# Sheet2_1.net
KiCad netlist of a schematic drawn in Altium Designer
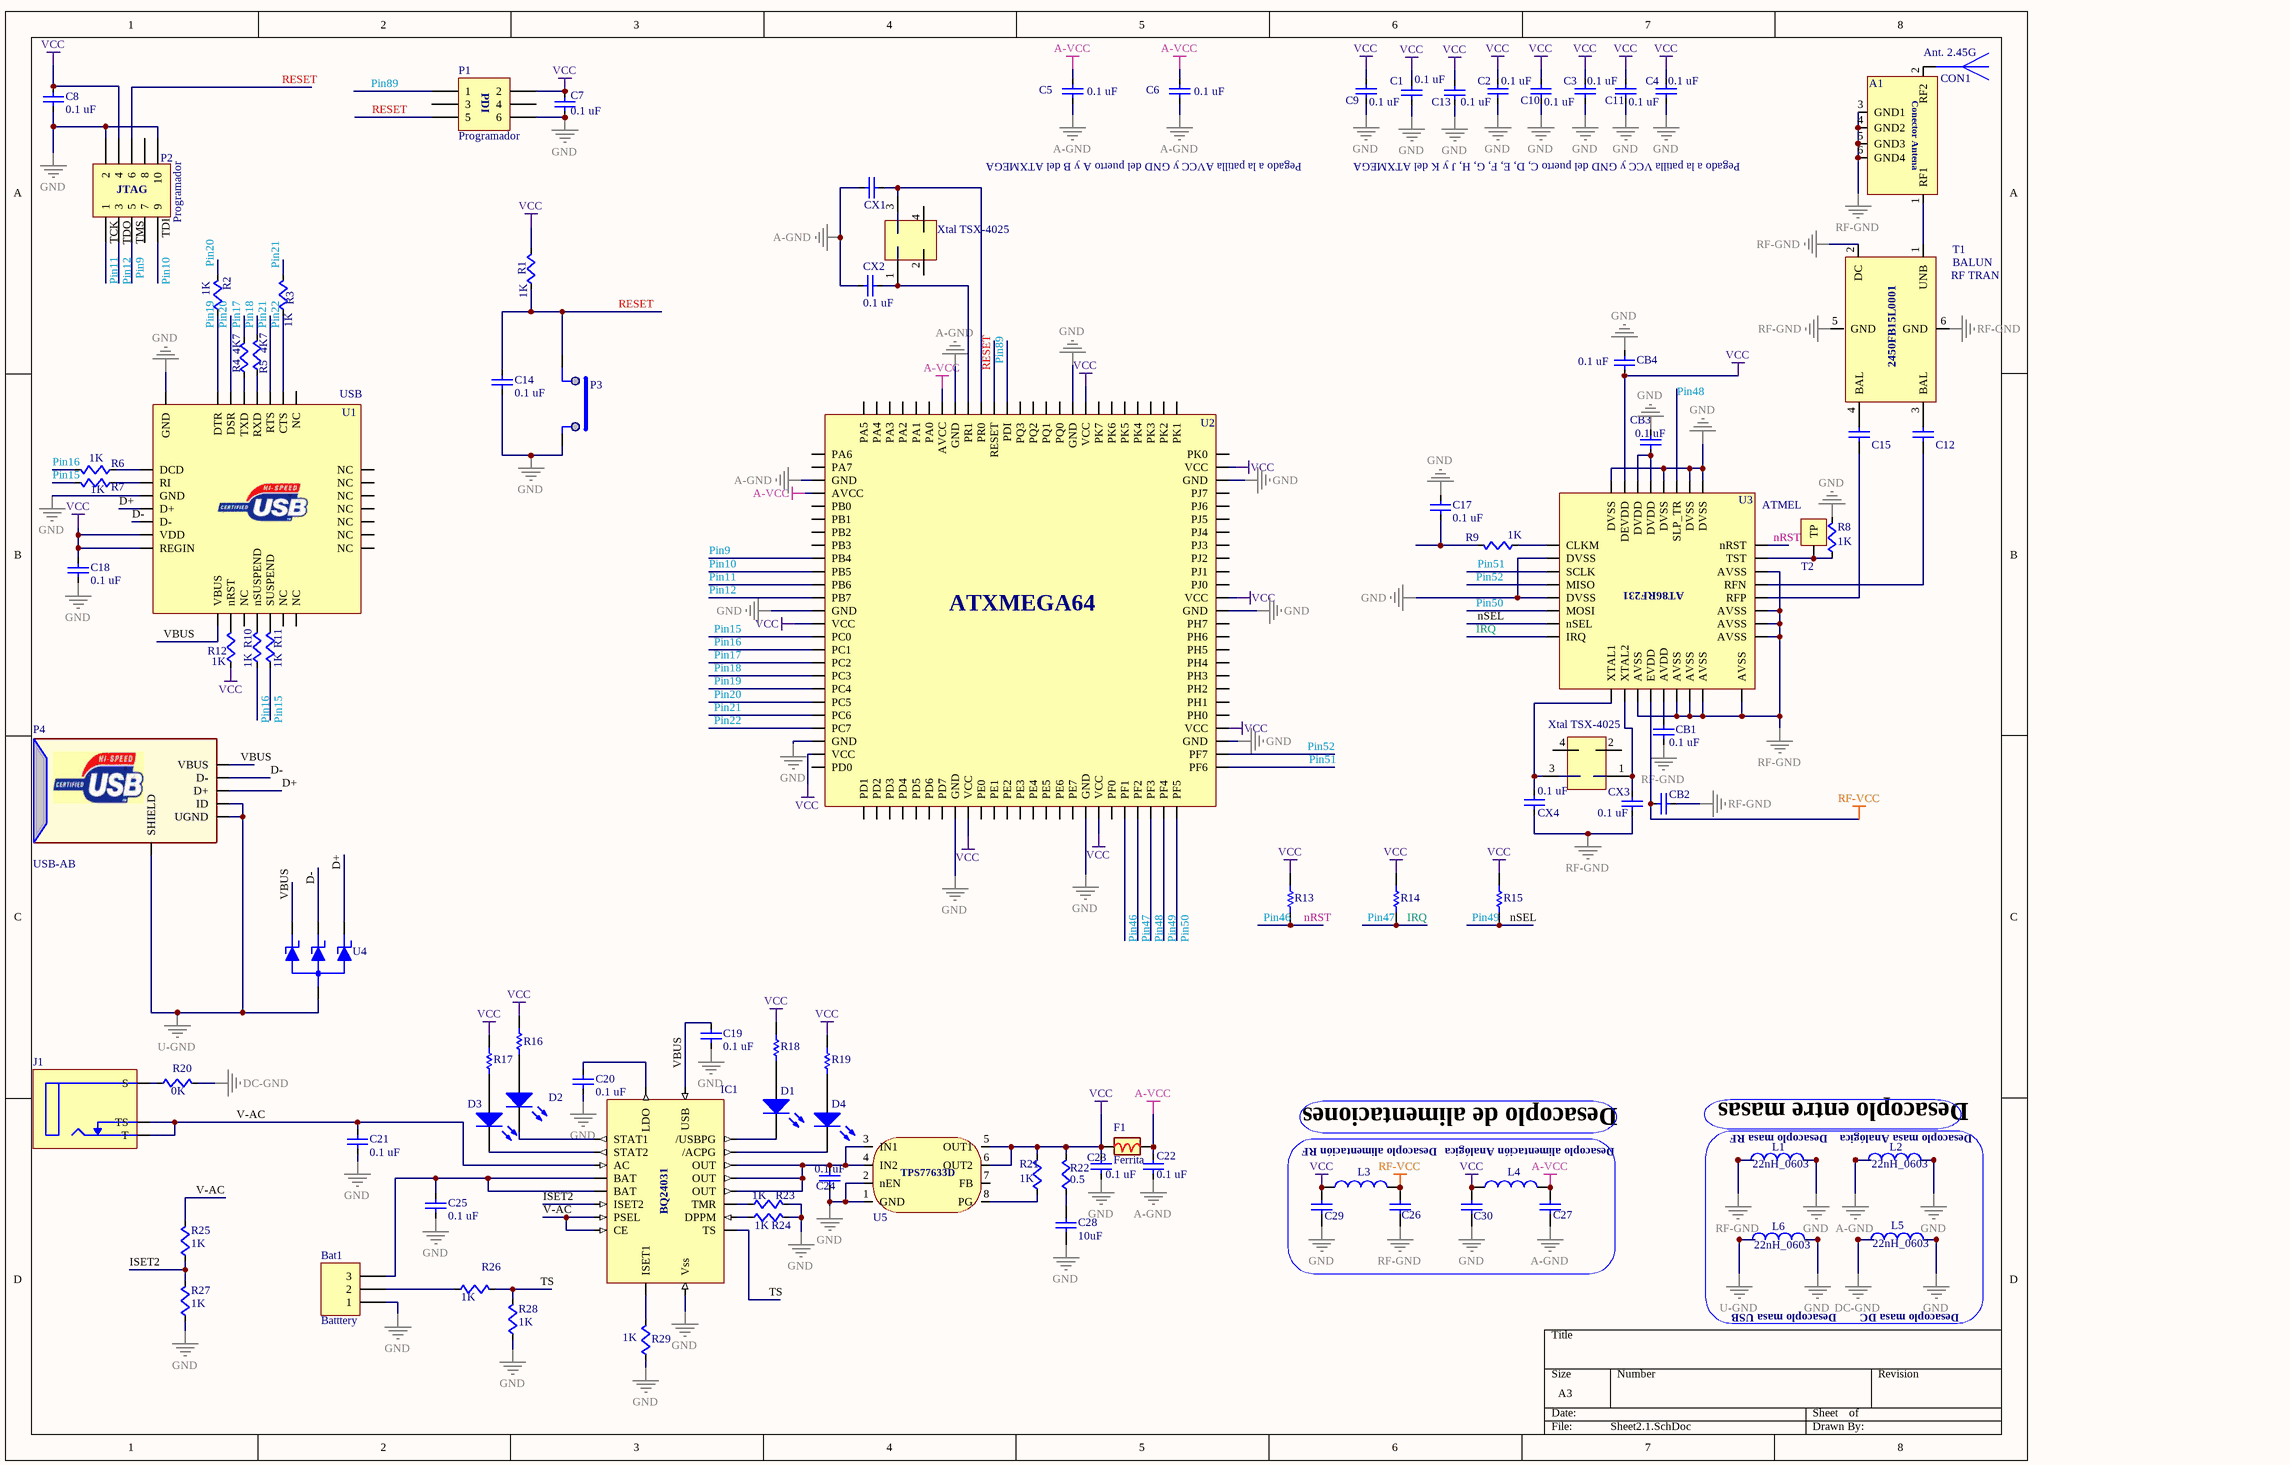
[diagram p0: Sheet2.1.SchDoc]

(export (version "E")
  (design (tool "Eeschema 10.0.6"))
  (components
    (comp (ref "A1")
      (value "Ant. 2.45G")
      (footprint "ANTENNA CHIP")
      (description "ANTENNA CHIP 2.4GHZ")
      (libsource (lib "Mia") (part "2450AT18A100"))
    )
    (comp (ref "Bat1")
      (value "Batttery")
      (footprint "HDR1X3")
      (description "Header, 3-Pin")
      (fields (field (name "PUBLISHER") "Altium Limited"))
      (libsource (lib "Mia") (part "Header 3"))
    )
    (comp (ref "C1")
      (value "C")
      (footprint "0402")
      (description "CONDENSADOR")
      (fields (field (name "VALOR") "0.1 uF"))
      (libsource (lib "Mia") (part "C"))
    )
    (comp (ref "C2")
      (value "C")
      (footprint "0402")
      (description "CONDENSADOR")
      (fields (field (name "VALOR") "0.1 uF"))
      (libsource (lib "Mia") (part "C"))
    )
    (comp (ref "C3")
      (value "C")
      (footprint "0402")
      (description "CONDENSADOR")
      (fields (field (name "VALOR") "0.1 uF"))
      (libsource (lib "Mia") (part "C"))
    )
    (comp (ref "C4")
      (value "C")
      (footprint "0402")
      (description "CONDENSADOR")
      (fields (field (name "VALOR") "0.1 uF"))
      (libsource (lib "Mia") (part "C"))
    )
    (comp (ref "C5")
      (value "C")
      (footprint "0402")
      (description "CONDENSADOR")
      (fields (field (name "VALOR") "0.1 uF"))
      (libsource (lib "Mia") (part "C"))
    )
    (comp (ref "C6")
      (value "C")
      (footprint "0402")
      (description "CONDENSADOR")
      (fields (field (name "VALOR") "0.1 uF"))
      (libsource (lib "Mia") (part "C"))
    )
    (comp (ref "C7")
      (value "C")
      (footprint "0402")
      (description "CONDENSADOR")
      (fields (field (name "VALOR") "0.1 uF"))
      (libsource (lib "Mia") (part "C"))
    )
    (comp (ref "C8")
      (value "C")
      (footprint "0402")
      (description "CONDENSADOR")
      (fields (field (name "VALOR") "0.1 uF"))
      (libsource (lib "Mia") (part "C"))
    )
    (comp (ref "C9")
      (value "C")
      (footprint "0402")
      (description "CONDENSADOR")
      (fields (field (name "VALOR") "0.1 uF"))
      (libsource (lib "Mia") (part "C"))
    )
    (comp (ref "C10")
      (value "C")
      (footprint "0402")
      (description "CONDENSADOR")
      (fields (field (name "VALOR") "0.1 uF"))
      (libsource (lib "Mia") (part "C"))
    )
    (comp (ref "C11")
      (value "C")
      (footprint "0402")
      (description "CONDENSADOR")
      (fields (field (name "VALOR") "0.1 uF"))
      (libsource (lib "Mia") (part "C"))
    )
    (comp (ref "C12")
      (value "22pF_0402")
      (footprint "0402")
      (description "CAP CER 56PF 50V 5% C0G 0402")
      (libsource (lib "Mia") (part "56pF_0402"))
    )
    (comp (ref "C13")
      (value "C")
      (footprint "0402")
      (description "CONDENSADOR")
      (fields (field (name "VALOR") "0.1 uF"))
      (libsource (lib "Mia") (part "C"))
    )
    (comp (ref "C14")
      (value "C")
      (footprint "0402")
      (description "CONDENSADOR")
      (fields (field (name "VALOR") "0.1 uF"))
      (libsource (lib "Mia") (part "C"))
    )
    (comp (ref "C15")
      (value "22pF_0402")
      (footprint "0402")
      (description "CAP CER 56PF 50V 5% C0G 0402")
      (libsource (lib "Mia") (part "56pF_0402"))
    )
    (comp (ref "C17")
      (value "C")
      (footprint "0402")
      (description "CONDENSADOR")
      (fields (field (name "VALOR") "0.1 uF"))
      (libsource (lib "Mia") (part "C"))
    )
    (comp (ref "C18")
      (value "C")
      (footprint "0402")
      (description "CONDENSADOR")
      (fields (field (name "VALOR") "0.1 uF"))
      (libsource (lib "Mia") (part "C"))
    )
    (comp (ref "C19")
      (value "C")
      (footprint "0402")
      (description "CONDENSADOR")
      (fields (field (name "VALOR") "0.1 uF"))
      (libsource (lib "Mia") (part "C"))
    )
    (comp (ref "C20")
      (value "C")
      (footprint "0402")
      (description "CONDENSADOR")
      (fields (field (name "VALOR") "0.1 uF"))
      (libsource (lib "Mia") (part "C"))
    )
    (comp (ref "C21")
      (value "C")
      (footprint "0402")
      (description "CONDENSADOR")
      (fields (field (name "VALOR") "0.1 uF"))
      (libsource (lib "Mia") (part "C"))
    )
    (comp (ref "C22")
      (value "C")
      (footprint "0402")
      (description "CONDENSADOR")
      (fields (field (name "VALOR") "0.1 uF"))
      (libsource (lib "Mia") (part "C"))
    )
    (comp (ref "C23")
      (value "C")
      (footprint "0402")
      (description "CONDENSADOR")
      (fields (field (name "VALOR") "0.1 uF"))
      (libsource (lib "Mia") (part "C"))
    )
    (comp (ref "C24")
      (value "C")
      (footprint "0402")
      (description "CONDENSADOR")
      (fields (field (name "VALOR") "0.1 uF"))
      (libsource (lib "Mia") (part "C"))
    )
    (comp (ref "C25")
      (value "C")
      (footprint "0402")
      (description "CONDENSADOR")
      (fields (field (name "VALOR") "0.1 uF"))
      (libsource (lib "Mia") (part "C"))
    )
    (comp (ref "C26")
      (value "100nF_0805")
      (footprint "0805")
      (description "CAP CER 100PF 630V X7R 0805")
      (libsource (lib "Mia") (part "100nF_0805"))
    )
    (comp (ref "C27")
      (value "100nF_0805")
      (footprint "0805")
      (description "CAP CER 100PF 630V X7R 0805")
      (libsource (lib "Mia") (part "100nF_0805"))
    )
    (comp (ref "C28")
      (value "10uF")
      (footprint "0805")
      (description "CAP CER 10UF 10V Y5V 0805")
      (libsource (lib "Mia") (part "10uF_0805"))
    )
    (comp (ref "C29")
      (value "100nF_0805")
      (footprint "0805")
      (description "CAP CER 100PF 630V X7R 0805")
      (libsource (lib "Mia") (part "100nF_0805"))
    )
    (comp (ref "C30")
      (value "100nF_0805")
      (footprint "0805")
      (description "CAP CER 100PF 630V X7R 0805")
      (libsource (lib "Mia") (part "100nF_0805"))
    )
    (comp (ref "CB1")
      (value "C")
      (footprint "0402")
      (description "CONDENSADOR")
      (fields (field (name "VALOR") "0.1 uF"))
      (libsource (lib "Mia") (part "C"))
    )
    (comp (ref "CB2")
      (value "C")
      (footprint "0402")
      (description "CONDENSADOR")
      (fields (field (name "VALOR") "0.1 uF"))
      (libsource (lib "Mia") (part "C"))
    )
    (comp (ref "CB3")
      (value "C")
      (footprint "0402")
      (description "CONDENSADOR")
      (fields (field (name "VALOR") "0.1 uF"))
      (libsource (lib "Mia") (part "C"))
    )
    (comp (ref "CB4")
      (value "C")
      (footprint "0402")
      (description "CONDENSADOR")
      (fields (field (name "VALOR") "0.1 uF"))
      (libsource (lib "Mia") (part "C"))
    )
    (comp (ref "CON1")
      (value "Conector Antena")
      (footprint "MM8430-2600_Coaxial Connectors")
      (description "CONN MW COAXIAL WITH SWITCH")
      (libsource (lib "Mia") (part "CON ANT-MM8430-2600RA1"))
    )
    (comp (ref "CX1")
      (value "C")
      (footprint "0402")
      (description "CONDENSADOR")
      (libsource (lib "Mia") (part "C"))
    )
    (comp (ref "CX2")
      (value "C")
      (footprint "0402")
      (description "CONDENSADOR")
      (fields (field (name "VALOR") "0.1 uF"))
      (libsource (lib "Mia") (part "C"))
    )
    (comp (ref "CX3")
      (value "C")
      (footprint "0402")
      (description "CONDENSADOR")
      (fields (field (name "VALOR") "0.1 uF"))
      (libsource (lib "Mia") (part "C"))
    )
    (comp (ref "CX4")
      (value "C")
      (footprint "0402")
      (description "CONDENSADOR")
      (libsource (lib "Mia") (part "C"))
    )
    (comp (ref "D1")
      (value "Diodo Led")
      (footprint "Diode Led")
      (description "Typical INFRARED GaAs LED")
      (libsource (lib "Mia") (part "LTST-C230CKT"))
    )
    (comp (ref "D2")
      (value "Diodo Led")
      (footprint "Diode Led")
      (description "Typical INFRARED GaAs LED")
      (libsource (lib "Mia") (part "LTST-C230CKT"))
    )
    (comp (ref "D3")
      (value "Diodo Led")
      (footprint "Diode Led")
      (description "Typical INFRARED GaAs LED")
      (libsource (lib "Mia") (part "LTST-C230CKT"))
    )
    (comp (ref "D4")
      (value "Diodo Led")
      (footprint "Diode Led")
      (description "Typical INFRARED GaAs LED")
      (libsource (lib "Mia") (part "LTST-C230CKT"))
    )
    (comp (ref "F1")
      (value "Ferrita")
      (footprint "0603")
      (description "Chip Ferrite Beads")
      (libsource (lib "Mia") (part "BLM21AH102SN1"))
    )
    (comp (ref "IC1")
      (value "BQ24031")
      (footprint "BQ24031")
      (description "IC PWR MANAGEMENT SYSTEM 20-QFN")
      (libsource (lib "Mia") (part "BQ24031"))
    )
    (comp (ref "J1")
      (value "CAMSHOT")
      (footprint "MJ-2509N")
      (description "CONN MONO JACK 2.5MM PCB MNT")
      (libsource (lib "*") (part "MJ-2509N_1"))
    )
    (comp (ref "L1")
      (value "22nH_0603")
      (footprint "0603")
      (description "CER INDUCTOR 22NH 0603")
      (libsource (lib "Mia") (part "22nH_0603"))
    )
    (comp (ref "L2")
      (value "22nH_0603")
      (footprint "0603")
      (description "CER INDUCTOR 22NH 0603")
      (libsource (lib "Mia") (part "22nH_0603"))
    )
    (comp (ref "L3")
      (value "22nH_0603")
      (footprint "0603")
      (description "CER INDUCTOR 22NH 0603")
      (libsource (lib "Mia") (part "22nH_0603"))
    )
    (comp (ref "L4")
      (value "22nH_0603")
      (footprint "0603")
      (description "CER INDUCTOR 22NH 0603")
      (libsource (lib "Mia") (part "22nH_0603"))
    )
    (comp (ref "L5")
      (value "22nH_0603")
      (footprint "0603")
      (description "CER INDUCTOR 22NH 0603")
      (libsource (lib "Mia") (part "22nH_0603"))
    )
    (comp (ref "L6")
      (value "22nH_0603")
      (footprint "0603")
      (description "CER INDUCTOR 22NH 0603")
      (libsource (lib "Mia") (part "22nH_0603"))
    )
    (comp (ref "P1")
      (value "Programador")
      (footprint "HDR2X3")
      (description "Header, 3-Pin, Dual row")
      (fields (field (name "PUBLISHER") "Altium Limited"))
      (libsource (lib "Mia") (part "Header 3X2"))
    )
    (comp (ref "P2")
      (value "Programador")
      (footprint "HDR2X5")
      (description "Header, 5-Pin, Dual row")
      (fields (field (name "PUBLISHER") "Altium Limited"))
      (libsource (lib "Mia") (part "Header 5X2"))
    )
    (comp (ref "P3")
      (value "Pulsador")
      (footprint "PUSH-BUTTON-W")
      (description "SWITCH TACT 6X3.5MM H=4.3MM 180G")
      (libsource (lib "Mia") (part "PUSHBUTTON"))
    )
    (comp (ref "P4")
      (value "USB-AB")
      (footprint "USB-MINI-AB-SMT")
      (description "CONN RECEPT USB 5POS RT ANG SMD")
      (libsource (lib "Mia") (part "WM1722"))
    )
    (comp (ref "R1")
      (value "1K")
      (footprint "0603")
      (description "RESISTENCIA 0402 SMD")
      (fields (field (name "Comment") "R 0402"))
      (libsource (lib "Mia") (part "R 0402"))
    )
    (comp (ref "R2")
      (value "1K")
      (footprint "0603")
      (description "RESISTENCIA 0402 SMD")
      (fields (field (name "Comment") "R 0402"))
      (libsource (lib "Mia") (part "R 0402"))
    )
    (comp (ref "R3")
      (value "1K")
      (footprint "0603")
      (description "RESISTENCIA 0402 SMD")
      (fields (field (name "Comment") "R 0402"))
      (libsource (lib "Mia") (part "R 0402"))
    )
    (comp (ref "R4")
      (value "4K7")
      (footprint "0603")
      (description "RESISTENCIA 0402 SMD")
      (fields (field (name "Comment") "R 0402"))
      (libsource (lib "Mia") (part "R 0402"))
    )
    (comp (ref "R5")
      (value "4K7")
      (footprint "0603")
      (description "RESISTENCIA 0402 SMD")
      (fields (field (name "Comment") "R 0402"))
      (libsource (lib "Mia") (part "R 0402"))
    )
    (comp (ref "R6")
      (value "1K")
      (footprint "0603")
      (description "RESISTENCIA 0402 SMD")
      (fields (field (name "Comment") "R 0402"))
      (libsource (lib "Mia") (part "R 0402"))
    )
    (comp (ref "R7")
      (value "1K")
      (footprint "0603")
      (description "RESISTENCIA 0402 SMD")
      (fields (field (name "Comment") "R 0402"))
      (libsource (lib "Mia") (part "R 0402"))
    )
    (comp (ref "R8")
      (value "1K")
      (footprint "0603")
      (description "RESISTENCIA 0402 SMD")
      (fields (field (name "Comment") "R 0402"))
      (libsource (lib "Mia") (part "R 0402"))
    )
    (comp (ref "R9")
      (value "1K")
      (footprint "0603")
      (description "RESISTENCIA 0402 SMD")
      (fields (field (name "Comment") "R 0402"))
      (libsource (lib "Mia") (part "R 0402"))
    )
    (comp (ref "R10")
      (value "1K")
      (footprint "0603")
      (description "RESISTENCIA 0402 SMD")
      (fields (field (name "Comment") "R 0402"))
      (libsource (lib "Mia") (part "R 0402"))
    )
    (comp (ref "R11")
      (value "1K")
      (footprint "0603")
      (description "RESISTENCIA 0402 SMD")
      (fields (field (name "Comment") "R 0402"))
      (libsource (lib "Mia") (part "R 0402"))
    )
    (comp (ref "R12")
      (value "1K")
      (footprint "0603")
      (description "RESISTENCIA 0402 SMD")
      (fields (field (name "Comment") "R 0402"))
      (libsource (lib "Mia") (part "R 0402"))
    )
    (comp (ref "R13")
      (value "16.9kohm-0805")
      (footprint "0805")
      (description "RES 16.9K OHM 1/8W 1% 0805 SMD")
      (libsource (lib "Mia") (part "16.9kohm-0805"))
    )
    (comp (ref "R14")
      (value "16.9kohm-0805")
      (footprint "0805")
      (description "RES 16.9K OHM 1/8W 1% 0805 SMD")
      (libsource (lib "Mia") (part "16.9kohm-0805"))
    )
    (comp (ref "R15")
      (value "16.9kohm-0805")
      (footprint "0805")
      (description "RES 16.9K OHM 1/8W 1% 0805 SMD")
      (libsource (lib "Mia") (part "16.9kohm-0805"))
    )
    (comp (ref "R16")
      (value "16.9kohm-0805")
      (footprint "0805")
      (description "RES 16.9K OHM 1/8W 1% 0805 SMD")
      (libsource (lib "Mia") (part "16.9kohm-0805"))
    )
    (comp (ref "R17")
      (value "16.9kohm-0805")
      (footprint "0805")
      (description "RES 16.9K OHM 1/8W 1% 0805 SMD")
      (libsource (lib "Mia") (part "16.9kohm-0805"))
    )
    (comp (ref "R18")
      (value "16.9kohm-0805")
      (footprint "0805")
      (description "RES 16.9K OHM 1/8W 1% 0805 SMD")
      (libsource (lib "Mia") (part "16.9kohm-0805"))
    )
    (comp (ref "R19")
      (value "16.9kohm-0805")
      (footprint "0805")
      (description "RES 16.9K OHM 1/8W 1% 0805 SMD")
      (libsource (lib "Mia") (part "16.9kohm-0805"))
    )
    (comp (ref "R20")
      (value "0K")
      (footprint "0603")
      (description "RESISTENCIA 0402 SMD")
      (fields (field (name "Comment") "R 0402"))
      (libsource (lib "Mia") (part "R 0402"))
    )
    (comp (ref "R21")
      (value "1K")
      (footprint "0603")
      (description "RESISTENCIA 0402 SMD")
      (fields (field (name "Comment") "R 0402"))
      (libsource (lib "Mia") (part "R 0402"))
    )
    (comp (ref "R22")
      (value "0.5")
      (footprint "0603")
      (description "RESISTENCIA 0402 SMD")
      (fields (field (name "Comment") "R 0402"))
      (libsource (lib "Mia") (part "R 0402"))
    )
    (comp (ref "R23")
      (value "1K")
      (footprint "0603")
      (description "RESISTENCIA 0402 SMD")
      (fields (field (name "Comment") "R 0402"))
      (libsource (lib "Mia") (part "R 0402"))
    )
    (comp (ref "R24")
      (value "1K")
      (footprint "0603")
      (description "RESISTENCIA 0402 SMD")
      (fields (field (name "Comment") "R 0402"))
      (libsource (lib "Mia") (part "R 0402"))
    )
    (comp (ref "R25")
      (value "1K")
      (footprint "0603")
      (description "RESISTENCIA 0402 SMD")
      (fields (field (name "Comment") "R 0402"))
      (libsource (lib "Mia") (part "R 0402"))
    )
    (comp (ref "R26")
      (value "1K")
      (footprint "0603")
      (description "RESISTENCIA 0402 SMD")
      (fields (field (name "Comment") "R 0402"))
      (libsource (lib "Mia") (part "R 0402"))
    )
    (comp (ref "R27")
      (value "1K")
      (footprint "0603")
      (description "RESISTENCIA 0402 SMD")
      (fields (field (name "Comment") "R 0402"))
      (libsource (lib "Mia") (part "R 0402"))
    )
    (comp (ref "R28")
      (value "1K")
      (footprint "0603")
      (description "RESISTENCIA 0402 SMD")
      (fields (field (name "Comment") "R 0402"))
      (libsource (lib "Mia") (part "R 0402"))
    )
    (comp (ref "R29")
      (value "1K")
      (footprint "0603")
      (description "RESISTENCIA 0402 SMD")
      (fields (field (name "Comment") "R 0402"))
      (libsource (lib "Mia") (part "R 0402"))
    )
    (comp (ref "T1")
      (value "BALUN")
      (footprint "BALUN")
      (description "FILTER BALUN CER CHIP 2.4GHZ")
      (libsource (lib "Mia") (part "2450FB39B100E"))
    )
    (comp (ref "T2")
      (value "TESTPOINT")
      (footprint "TESTPOINT")
      (description "Punto de Test")
      (libsource (lib "Mia") (part "TESTPOINT"))
    )
    (comp (ref "U1")
      (value "USB")
      (footprint "QFN28_5X5")
      (description "IC USB-TO-UART BRIDGE 28MLP")
      (libsource (lib "Mia") (part "CP2102"))
    )
    (comp (ref "U2")
      (value "XMEGA")
      (footprint "Quad100")
      (description "MCU AVR 64K FLASH 1.6V 100-TQFP")
      (libsource (lib "Mia") (part "ATXMEGA64A1"))
    )
    (comp (ref "U3")
      (value "RF TRAN")
      (footprint "QFN32_50")
      (description "IC TXRX ZIGBEE/802.15.4 32QFN")
      (fields (field (name "FABRICANTE") "ATMEL"))
      (libsource (lib "Mia") (part "AT86RF231"))
    )
    (comp (ref "U4")
      (value "TVS")
      (footprint "SOT-143")
      (description "TVS AVAL DIODE ARRAY 3 CH SOT143")
      (libsource (lib "Mia") (part "SP0503BAHTG"))
    )
    (comp (ref "U5")
      (value "TPS77633D")
      (footprint "TPS77633D")
      (description "IC 3.3V 500MA LDO REG 8-SOIC")
      (libsource (lib "Mia") (part "TPS77633D"))
    )
    (comp (ref "Xtal1")
      (value "Xtal TSX-4025")
      (footprint "TSX-4025")
      (description "Cristal 16Mhz")
      (libsource (lib "") (part "Xtal TSX-4025_1"))
    )
    (comp (ref "Xtal2")
      (value "Xtal TSX-4025")
      (footprint "TSX-4025")
      (description "Cristal 16Mhz")
      (libsource (lib "Mia") (part "Xtal TSX-4025"))
    )
  )
  (nets
    (net (code "1") (name "/D+") (class "Default")
      (node (ref "P4") (pin "D+") (pinfunction "D+_D+") (pintype "passive"))
      (node (ref "U1") (pin "4") (pinfunction "D+_4") (pintype "passive"))
      (node (ref "U4") (pin "2") (pinfunction "C_2") (pintype "passive"))
    )
    (net (code "2") (name "/D-") (class "Default")
      (node (ref "P4") (pin "D-") (pinfunction "D-_D-") (pintype "passive"))
      (node (ref "U1") (pin "5") (pinfunction "D-_5") (pintype "passive"))
      (node (ref "U4") (pin "3") (pinfunction "C_3") (pintype "passive"))
    )
    (net (code "3") (name "/IRQ") (class "Default")
      (node (ref "R14") (pin "1") (pinfunction "1_1") (pintype "passive"))
      (node (ref "U2") (pin "47") (pinfunction "PF2_47") (pintype "passive"))
      (node (ref "U3") (pin "24") (pinfunction "IRQ_24") (pintype "passive"))
    )
    (net (code "4") (name "/ISET2") (class "Default")
      (node (ref "IC1") (pin "7") (pinfunction "ISET2_7") (pintype "input"))
      (node (ref "R25") (pin "1") (pinfunction "1_1") (pintype "passive"))
      (node (ref "R27") (pin "2") (pinfunction "2_2") (pintype "passive"))
    )
    (net (code "5") (name "/Pin9") (class "Default")
      (node (ref "P2") (pin "5") (pinfunction "5_5") (pintype "passive"))
      (node (ref "U2") (pin "9") (pinfunction "PB4_9") (pintype "passive"))
    )
    (net (code "6") (name "/Pin10") (class "Default")
      (node (ref "P2") (pin "9") (pinfunction "9_9") (pintype "passive"))
      (node (ref "U2") (pin "10") (pinfunction "PB5_10") (pintype "passive"))
    )
    (net (code "7") (name "/Pin11") (class "Default")
      (node (ref "P2") (pin "1") (pinfunction "1_1") (pintype "passive"))
      (node (ref "U2") (pin "11") (pinfunction "PB6_11") (pintype "passive"))
    )
    (net (code "8") (name "/Pin12") (class "Default")
      (node (ref "P2") (pin "3") (pinfunction "3_3") (pintype "passive"))
      (node (ref "U2") (pin "12") (pinfunction "PB7_12") (pintype "passive"))
    )
    (net (code "9") (name "/Pin15") (class "Default")
      (node (ref "R11") (pin "1") (pinfunction "1_1") (pintype "passive"))
      (node (ref "R7") (pin "2") (pinfunction "2_2") (pintype "passive"))
      (node (ref "U2") (pin "15") (pinfunction "PC0_15") (pintype "passive"))
    )
    (net (code "10") (name "/Pin16") (class "Default")
      (node (ref "R10") (pin "1") (pinfunction "1_1") (pintype "passive"))
      (node (ref "R6") (pin "2") (pinfunction "2_2") (pintype "passive"))
      (node (ref "U2") (pin "16") (pinfunction "PC1_16") (pintype "passive"))
    )
    (net (code "11") (name "/Pin17") (class "Default")
      (node (ref "R4") (pin "2") (pinfunction "2_2") (pintype "passive"))
      (node (ref "U2") (pin "17") (pinfunction "PC2_17") (pintype "passive"))
    )
    (net (code "12") (name "/Pin18") (class "Default")
      (node (ref "R5") (pin "2") (pinfunction "2_2") (pintype "passive"))
      (node (ref "U2") (pin "18") (pinfunction "PC3_18") (pintype "passive"))
    )
    (net (code "13") (name "/Pin19") (class "Default")
      (node (ref "R2") (pin "1") (pinfunction "1_1") (pintype "passive"))
      (node (ref "U1") (pin "28") (pinfunction "DTR_28") (pintype "passive"))
      (node (ref "U2") (pin "19") (pinfunction "PC4_19") (pintype "passive"))
    )
    (net (code "14") (name "/Pin20") (class "Default")
      (node (ref "R2") (pin "2") (pinfunction "2_2") (pintype "passive"))
      (node (ref "U1") (pin "27") (pinfunction "DSR_27") (pintype "passive"))
      (node (ref "U2") (pin "20") (pinfunction "PC5_20") (pintype "passive"))
    )
    (net (code "15") (name "/Pin21") (class "Default")
      (node (ref "R3") (pin "2") (pinfunction "2_2") (pintype "passive"))
      (node (ref "U1") (pin "24") (pinfunction "RTS_24") (pintype "passive"))
      (node (ref "U2") (pin "21") (pinfunction "PC6_21") (pintype "passive"))
    )
    (net (code "16") (name "/Pin22") (class "Default")
      (node (ref "R3") (pin "1") (pinfunction "1_1") (pintype "passive"))
      (node (ref "U1") (pin "23") (pinfunction "CTS_23") (pintype "passive"))
      (node (ref "U2") (pin "22") (pinfunction "PC7_22") (pintype "passive"))
    )
    (net (code "17") (name "/Pin46") (class "Default")
      (node (ref "R13") (pin "1") (pinfunction "1_1") (pintype "passive"))
      (node (ref "U2") (pin "46") (pinfunction "PF1_46") (pintype "passive"))
      (node (ref "U3") (pin "8") (pinfunction "nRST_8") (pintype "passive"))
    )
    (net (code "18") (name "/Pin48") (class "Default")
      (node (ref "U2") (pin "48") (pinfunction "PF3_48") (pintype "passive"))
      (node (ref "U3") (pin "11") (pinfunction "SLP_TR_11") (pintype "passive"))
    )
    (net (code "19") (name "/Pin49") (class "Default")
      (node (ref "R15") (pin "1") (pinfunction "1_1") (pintype "passive"))
      (node (ref "U2") (pin "49") (pinfunction "PF4_49") (pintype "passive"))
      (node (ref "U3") (pin "23") (pinfunction "nSEL_23") (pintype "passive"))
    )
    (net (code "20") (name "/Pin50") (class "Default")
      (node (ref "U2") (pin "50") (pinfunction "PF5_50") (pintype "passive"))
      (node (ref "U3") (pin "22") (pinfunction "MOSI_22") (pintype "passive"))
    )
    (net (code "21") (name "/Pin51") (class "Default")
      (node (ref "U2") (pin "51") (pinfunction "PF6_51") (pintype "passive"))
      (node (ref "U3") (pin "19") (pinfunction "SCLK_19") (pintype "passive"))
    )
    (net (code "22") (name "/Pin52") (class "Default")
      (node (ref "U2") (pin "52") (pinfunction "PF7_52") (pintype "passive"))
      (node (ref "U3") (pin "20") (pinfunction "MISO_20") (pintype "passive"))
    )
    (net (code "23") (name "/Pin89") (class "Default")
      (node (ref "P1") (pin "1") (pinfunction "1_1") (pintype "passive"))
      (node (ref "U2") (pin "89") (pinfunction "PDI_89") (pintype "passive"))
    )
    (net (code "24") (name "/RESET") (class "Default")
      (node (ref "C14") (pin "1") (pinfunction "1_1") (pintype "passive"))
      (node (ref "P1") (pin "5") (pinfunction "5_5") (pintype "passive"))
      (node (ref "P2") (pin "6") (pinfunction "6_6") (pintype "passive"))
      (node (ref "P3") (pin "1") (pinfunction "1_1") (pintype "passive"))
      (node (ref "R1") (pin "1") (pinfunction "1_1") (pintype "passive"))
      (node (ref "U2") (pin "90") (pinfunction "RESET_90") (pintype "passive"))
    )
    (net (code "29") (name "/TS") (class "Default")
      (node (ref "IC1") (pin "12") (pinfunction "TS_12") (pintype "bidirectional"))
      (node (ref "R26") (pin "2") (pinfunction "2_2") (pintype "passive"))
      (node (ref "R28") (pin "2") (pinfunction "2_2") (pintype "passive"))
    )
    (net (code "30") (name "/V-AC") (class "Default")
      (node (ref "C21") (pin "1") (pinfunction "1_1") (pintype "passive"))
      (node (ref "IC1") (pin "4") (pinfunction "AC_4") (pintype "input"))
      (node (ref "IC1") (pin "8") (pinfunction "PSEL_8") (pintype "input"))
      (node (ref "IC1") (pin "9") (pinfunction "CE_9") (pintype "input"))
      (node (ref "J1") (pin "2") (pinfunction "T_2") (pintype "passive"))
      (node (ref "J1") (pin "3") (pinfunction "TS_3") (pintype "passive"))
      (node (ref "R25") (pin "2") (pinfunction "2_2") (pintype "passive"))
    )
    (net (code "31") (name "/VBUS") (class "Default")
      (node (ref "C19") (pin "1") (pinfunction "1_1") (pintype "passive"))
      (node (ref "IC1") (pin "20") (pinfunction "USB_20") (pintype "input"))
      (node (ref "P4") (pin "VBUS") (pinfunction "VBUS_VBUS") (pintype "passive"))
      (node (ref "U1") (pin "8") (pinfunction "VBUS_8") (pintype "passive"))
      (node (ref "U4") (pin "4") (pinfunction "C_4") (pintype "passive"))
    )
    (net (code "32") (name "A-GND") (class "Default")
      (node (ref "C22") (pin "2") (pinfunction "2_2") (pintype "passive"))
      (node (ref "C27") (pin "1") (pinfunction "1_1") (pintype "passive"))
      (node (ref "C5") (pin "2") (pinfunction "2_2") (pintype "passive"))
      (node (ref "C6") (pin "2") (pinfunction "2_2") (pintype "passive"))
      (node (ref "CX1") (pin "1") (pinfunction "1_1") (pintype "passive"))
      (node (ref "CX2") (pin "1") (pinfunction "1_1") (pintype "passive"))
      (node (ref "L2") (pin "1") (pinfunction "1_1") (pintype "passive"))
      (node (ref "U2") (pin "3") (pinfunction "GND_3") (pintype "passive"))
      (node (ref "U2") (pin "93") (pinfunction "GND_93") (pintype "passive"))
    )
    (net (code "33") (name "A-VCC") (class "Default")
      (node (ref "C22") (pin "1") (pinfunction "1_1") (pintype "passive"))
      (node (ref "C27") (pin "2") (pinfunction "2_2") (pintype "passive"))
      (node (ref "C5") (pin "1") (pinfunction "1_1") (pintype "passive"))
      (node (ref "C6") (pin "1") (pinfunction "1_1") (pintype "passive"))
      (node (ref "F1") (pin "2") (pinfunction "Y_2") (pintype "passive"))
      (node (ref "L4") (pin "2") (pinfunction "2_2") (pintype "passive"))
      (node (ref "U2") (pin "4") (pinfunction "AVCC_4") (pintype "passive"))
      (node (ref "U2") (pin "94") (pinfunction "AVCC_94") (pintype "passive"))
    )
    (net (code "34") (name "DC-GND") (class "Default")
      (node (ref "L5") (pin "1") (pinfunction "1_1") (pintype "passive"))
      (node (ref "R20") (pin "2") (pinfunction "2_2") (pintype "passive"))
    )
    (net (code "35") (name "GND") (class "Default")
      (node (ref "Bat1") (pin "1") (pinfunction "1_1") (pintype "passive"))
      (node (ref "C1") (pin "2") (pinfunction "2_2") (pintype "passive"))
      (node (ref "C10") (pin "2") (pinfunction "2_2") (pintype "passive"))
      (node (ref "C11") (pin "2") (pinfunction "2_2") (pintype "passive"))
      (node (ref "C13") (pin "2") (pinfunction "2_2") (pintype "passive"))
      (node (ref "C14") (pin "2") (pinfunction "2_2") (pintype "passive"))
      (node (ref "C17") (pin "1") (pinfunction "1_1") (pintype "passive"))
      (node (ref "C18") (pin "2") (pinfunction "2_2") (pintype "passive"))
      (node (ref "C19") (pin "2") (pinfunction "2_2") (pintype "passive"))
      (node (ref "C2") (pin "2") (pinfunction "2_2") (pintype "passive"))
      (node (ref "C20") (pin "2") (pinfunction "2_2") (pintype "passive"))
      (node (ref "C21") (pin "2") (pinfunction "2_2") (pintype "passive"))
      (node (ref "C23") (pin "2") (pinfunction "2_2") (pintype "passive"))
      (node (ref "C24") (pin "2") (pinfunction "2_2") (pintype "passive"))
      (node (ref "C25") (pin "2") (pinfunction "2_2") (pintype "passive"))
      (node (ref "C28") (pin "1") (pinfunction "1_1") (pintype "passive"))
      (node (ref "C29") (pin "1") (pinfunction "1_1") (pintype "passive"))
      (node (ref "C3") (pin "2") (pinfunction "2_2") (pintype "passive"))
      (node (ref "C30") (pin "1") (pinfunction "1_1") (pintype "passive"))
      (node (ref "C4") (pin "2") (pinfunction "2_2") (pintype "passive"))
      (node (ref "C7") (pin "2") (pinfunction "2_2") (pintype "passive"))
      (node (ref "C8") (pin "2") (pinfunction "2_2") (pintype "passive"))
      (node (ref "C9") (pin "2") (pinfunction "2_2") (pintype "passive"))
      (node (ref "CB3") (pin "1") (pinfunction "1_1") (pintype "passive"))
      (node (ref "CB4") (pin "2") (pinfunction "2_2") (pintype "passive"))
      (node (ref "IC1") (pin "11") (pinfunction "Vss_11") (pintype "input"))
      (node (ref "L1") (pin "2") (pinfunction "2_2") (pintype "passive"))
      (node (ref "L2") (pin "2") (pinfunction "2_2") (pintype "passive"))
      (node (ref "L5") (pin "2") (pinfunction "2_2") (pintype "passive"))
      (node (ref "L6") (pin "2") (pinfunction "2_2") (pintype "passive"))
      (node (ref "P1") (pin "6") (pinfunction "6_6") (pintype "passive"))
      (node (ref "P2") (pin "10") (pinfunction "10_10") (pintype "passive"))
      (node (ref "P2") (pin "2") (pinfunction "2_2") (pintype "passive"))
      (node (ref "P3") (pin "2") (pinfunction "2_2") (pintype "passive"))
      (node (ref "R23") (pin "2") (pinfunction "2_2") (pintype "passive"))
      (node (ref "R24") (pin "2") (pinfunction "2_2") (pintype "passive"))
      (node (ref "R27") (pin "1") (pinfunction "1_1") (pintype "passive"))
      (node (ref "R28") (pin "1") (pinfunction "1_1") (pintype "passive"))
      (node (ref "R29") (pin "1") (pinfunction "1_1") (pintype "passive"))
      (node (ref "R8") (pin "2") (pinfunction "2_2") (pintype "passive"))
      (node (ref "U1") (pin "0") (pinfunction "GND_0") (pintype "passive"))
      (node (ref "U1") (pin "3") (pinfunction "GND_3") (pintype "passive"))
      (node (ref "U2") (pin "13") (pinfunction "GND_13") (pintype "passive"))
      (node (ref "U2") (pin "23") (pinfunction "GND_23") (pintype "passive"))
      (node (ref "U2") (pin "33") (pinfunction "GND_33") (pintype "passive"))
      (node (ref "U2") (pin "43") (pinfunction "GND_43") (pintype "passive"))
      (node (ref "U2") (pin "53") (pinfunction "GND_53") (pintype "passive"))
      (node (ref "U2") (pin "63") (pinfunction "GND_63") (pintype "passive"))
      (node (ref "U2") (pin "73") (pinfunction "GND_73") (pintype "passive"))
      (node (ref "U2") (pin "84") (pinfunction "GND_84") (pintype "passive"))
      (node (ref "U3") (pin "10") (pinfunction "DVSS_10") (pintype "passive"))
      (node (ref "U3") (pin "12") (pinfunction "DVSS_12") (pintype "passive"))
      (node (ref "U3") (pin "16") (pinfunction "DVSS_16") (pintype "passive"))
      (node (ref "U3") (pin "18") (pinfunction "DVSS_18") (pintype "passive"))
      (node (ref "U3") (pin "21") (pinfunction "DVSS_21") (pintype "passive"))
      (node (ref "U3") (pin "9") (pinfunction "DVSS_9") (pintype "passive"))
      (node (ref "U5") (pin "1") (pinfunction "GND_1") (pintype "passive"))
      (node (ref "U5") (pin "2") (pinfunction "nEN_2") (pintype "passive"))
    )
    (net (code "36") (name "Net-(A1-OUT)") (class "Default")
      (node (ref "A1") (pin "1") (pinfunction "OUT_1") (pintype "passive"))
      (node (ref "CON1") (pin "2") (pinfunction "RF2_2") (pintype "passive"))
    )
    (net (code "37") (name "Net-(Bat1-Pad2)") (class "Default")
      (node (ref "Bat1") (pin "2") (pinfunction "2_2") (pintype "passive"))
      (node (ref "R26") (pin "1") (pinfunction "1_1") (pintype "passive"))
    )
    (net (code "38") (name "Net-(Bat1-Pad3)") (class "Default")
      (node (ref "Bat1") (pin "3") (pinfunction "3_3") (pintype "passive"))
      (node (ref "C25") (pin "1") (pinfunction "1_1") (pintype "passive"))
      (node (ref "IC1") (pin "5") (pinfunction "BAT_5") (pintype "bidirectional"))
      (node (ref "IC1") (pin "6") (pinfunction "BAT_6") (pintype "bidirectional"))
    )
    (net (code "39") (name "Net-(C12-Pad2)") (class "Default")
      (node (ref "C12") (pin "2") (pinfunction "2_2") (pintype "passive"))
      (node (ref "T1") (pin "3") (pinfunction "BAL_3") (pintype "passive"))
    )
    (net (code "40") (name "Net-(C15-Pad2)") (class "Default")
      (node (ref "C15") (pin "2") (pinfunction "2_2") (pintype "passive"))
      (node (ref "T1") (pin "4") (pinfunction "BAL_4") (pintype "passive"))
    )
    (net (code "41") (name "Net-(C17-Pad2)") (class "Default")
      (node (ref "C17") (pin "2") (pinfunction "2_2") (pintype "passive"))
      (node (ref "R9") (pin "2") (pinfunction "2_2") (pintype "passive"))
    )
    (net (code "42") (name "Net-(C28-Pad2)") (class "Default")
      (node (ref "C28") (pin "2") (pinfunction "2_2") (pintype "passive"))
      (node (ref "R22") (pin "1") (pinfunction "1_1") (pintype "passive"))
    )
    (net (code "43") (name "Net-(CB3-Pad2)") (class "Default")
      (node (ref "CB3") (pin "2") (pinfunction "2_2") (pintype "passive"))
      (node (ref "U3") (pin "13") (pinfunction "DVDD_13") (pintype "passive"))
      (node (ref "U3") (pin "14") (pinfunction "DVDD_14") (pintype "passive"))
    )
    (net (code "44") (name "Net-(CON1-RF1)") (class "Default")
      (node (ref "CON1") (pin "1") (pinfunction "RF1_1") (pintype "passive"))
      (node (ref "T1") (pin "1") (pinfunction "UNB_1") (pintype "passive"))
    )
    (net (code "45") (name "Net-(D1-A)") (class "Default")
      (node (ref "D1") (pin "1") (pinfunction "A_1") (pintype "passive"))
      (node (ref "R18") (pin "1") (pinfunction "1_1") (pintype "passive"))
    )
    (net (code "46") (name "Net-(D1-K)") (class "Default")
      (node (ref "D1") (pin "2") (pinfunction "K_2") (pintype "passive"))
      (node (ref "IC1") (pin "19") (pinfunction "/USBPG_19") (pintype "output"))
    )
    (net (code "47") (name "Net-(D2-A)") (class "Default")
      (node (ref "D2") (pin "1") (pinfunction "A_1") (pintype "passive"))
      (node (ref "R16") (pin "1") (pinfunction "1_1") (pintype "passive"))
    )
    (net (code "48") (name "Net-(D2-K)") (class "Default")
      (node (ref "D2") (pin "2") (pinfunction "K_2") (pintype "passive"))
      (node (ref "IC1") (pin "2") (pinfunction "STAT1_2") (pintype "output"))
    )
    (net (code "49") (name "Net-(D3-A)") (class "Default")
      (node (ref "D3") (pin "1") (pinfunction "A_1") (pintype "passive"))
      (node (ref "R17") (pin "1") (pinfunction "1_1") (pintype "passive"))
    )
    (net (code "50") (name "Net-(D3-K)") (class "Default")
      (node (ref "D3") (pin "2") (pinfunction "K_2") (pintype "passive"))
      (node (ref "IC1") (pin "3") (pinfunction "STAT2_3") (pintype "output"))
    )
    (net (code "51") (name "Net-(D4-A)") (class "Default")
      (node (ref "D4") (pin "1") (pinfunction "A_1") (pintype "passive"))
      (node (ref "R19") (pin "1") (pinfunction "1_1") (pintype "passive"))
    )
    (net (code "52") (name "Net-(D4-K)") (class "Default")
      (node (ref "D4") (pin "2") (pinfunction "K_2") (pintype "passive"))
      (node (ref "IC1") (pin "18") (pinfunction "/ACPG_18") (pintype "output"))
    )
    (net (code "53") (name "Net-(IC1-DPPM)") (class "Default")
      (node (ref "IC1") (pin "13") (pinfunction "DPPM_13") (pintype "input"))
      (node (ref "R23") (pin "1") (pinfunction "1_1") (pintype "passive"))
    )
    (net (code "54") (name "Net-(IC1-ISET1)") (class "Default")
      (node (ref "IC1") (pin "10") (pinfunction "ISET1_10") (pintype "bidirectional"))
      (node (ref "R29") (pin "2") (pinfunction "2_2") (pintype "passive"))
    )
    (net (code "55") (name "Net-(IC1-LDO)") (class "Default")
      (node (ref "C20") (pin "1") (pinfunction "1_1") (pintype "passive"))
      (node (ref "IC1") (pin "1") (pinfunction "LDO_1") (pintype "output"))
    )
    (net (code "56") (name "Net-(IC1-TMR)") (class "Default")
      (node (ref "IC1") (pin "14") (pinfunction "TMR_14") (pintype "bidirectional"))
      (node (ref "R24") (pin "1") (pinfunction "1_1") (pintype "passive"))
    )
    (net (code "57") (name "Net-(J1-S)") (class "Default")
      (node (ref "J1") (pin "1") (pinfunction "S_1") (pintype "passive"))
      (node (ref "R20") (pin "1") (pinfunction "1_1") (pintype "passive"))
    )
    (net (code "58") (name "Net-(T2-TP)") (class "Default")
      (node (ref "R8") (pin "1") (pinfunction "1_1") (pintype "passive"))
      (node (ref "T2") (pin "1") (pinfunction "TP_1") (pintype "passive"))
      (node (ref "U3") (pin "7") (pinfunction "TST_7") (pintype "passive"))
    )
    (net (code "59") (name "Net-(U1-DCD)") (class "Default")
      (node (ref "R6") (pin "1") (pinfunction "1_1") (pintype "passive"))
      (node (ref "U1") (pin "1") (pinfunction "DCD_1") (pintype "passive"))
    )
    (net (code "60") (name "Net-(U1-RI)") (class "Default")
      (node (ref "R7") (pin "1") (pinfunction "1_1") (pintype "passive"))
      (node (ref "U1") (pin "2") (pinfunction "RI_2") (pintype "passive"))
    )
    (net (code "61") (name "Net-(U1-RXD)") (class "Default")
      (node (ref "R5") (pin "1") (pinfunction "1_1") (pintype "passive"))
      (node (ref "U1") (pin "25") (pinfunction "RXD_25") (pintype "passive"))
    )
    (net (code "62") (name "Net-(U1-SUSPEND)") (class "Default")
      (node (ref "R11") (pin "2") (pinfunction "2_2") (pintype "passive"))
      (node (ref "U1") (pin "12") (pinfunction "SUSPEND_12") (pintype "passive"))
    )
    (net (code "63") (name "Net-(U1-TXD)") (class "Default")
      (node (ref "R4") (pin "1") (pinfunction "1_1") (pintype "passive"))
      (node (ref "U1") (pin "26") (pinfunction "TXD_26") (pintype "passive"))
    )
    (net (code "64") (name "Net-(U1-nRST)") (class "Default")
      (node (ref "R12") (pin "2") (pinfunction "2_2") (pintype "passive"))
      (node (ref "U1") (pin "9") (pinfunction "nRST_9") (pintype "passive"))
    )
    (net (code "65") (name "Net-(U1-nSUSPEND)") (class "Default")
      (node (ref "R10") (pin "2") (pinfunction "2_2") (pintype "passive"))
      (node (ref "U1") (pin "11") (pinfunction "nSUSPEND_11") (pintype "passive"))
    )
    (net (code "66") (name "Net-(U2-PR0)") (class "Default")
      (node (ref "CX1") (pin "2") (pinfunction "2_2") (pintype "passive"))
      (node (ref "U2") (pin "91") (pinfunction "PR0_91") (pintype "passive"))
      (node (ref "Xtal1") (pin "3") (pinfunction "OSC2_3") (pintype "passive"))
    )
    (net (code "67") (name "Net-(U2-PR1)") (class "Default")
      (node (ref "CX2") (pin "2") (pinfunction "2_2") (pintype "passive"))
      (node (ref "U2") (pin "92") (pinfunction "PR1_92") (pintype "passive"))
      (node (ref "Xtal1") (pin "1") (pinfunction "OSC1_1") (pintype "passive"))
    )
    (net (code "68") (name "Net-(U3-AVDD)") (class "Default")
      (node (ref "CB1") (pin "2") (pinfunction "2_2") (pintype "passive"))
      (node (ref "U3") (pin "29") (pinfunction "AVDD_29") (pintype "passive"))
    )
    (net (code "69") (name "Net-(U3-CLKM)") (class "Default")
      (node (ref "R9") (pin "1") (pinfunction "1_1") (pintype "passive"))
      (node (ref "U3") (pin "17") (pinfunction "CLKM_17") (pintype "passive"))
    )
    (net (code "70") (name "Net-(U3-RFN)") (class "Default")
      (node (ref "C12") (pin "1") (pinfunction "1_1") (pintype "passive"))
      (node (ref "U3") (pin "5") (pinfunction "RFN_5") (pintype "passive"))
    )
    (net (code "71") (name "Net-(U3-RFP)") (class "Default")
      (node (ref "C15") (pin "1") (pinfunction "1_1") (pintype "passive"))
      (node (ref "U3") (pin "4") (pinfunction "RFP_4") (pintype "passive"))
    )
    (net (code "72") (name "Net-(U3-XTAL1)") (class "Default")
      (node (ref "CX4") (pin "2") (pinfunction "2_2") (pintype "passive"))
      (node (ref "U3") (pin "25") (pinfunction "XTAL1_25") (pintype "passive"))
      (node (ref "Xtal2") (pin "3") (pinfunction "OSC2_3") (pintype "passive"))
    )
    (net (code "73") (name "Net-(U3-XTAL2)") (class "Default")
      (node (ref "CX3") (pin "2") (pinfunction "2_2") (pintype "passive"))
      (node (ref "U3") (pin "26") (pinfunction "XTAL2_26") (pintype "passive"))
      (node (ref "Xtal2") (pin "1") (pinfunction "OSC1_1") (pintype "passive"))
    )
    (net (code "74") (name "Net-(U5-IN1)") (class "Default")
      (node (ref "C24") (pin "1") (pinfunction "1_1") (pintype "passive"))
      (node (ref "IC1") (pin "15") (pinfunction "OUT_15") (pintype "output"))
      (node (ref "IC1") (pin "16") (pinfunction "OUT_16") (pintype "output"))
      (node (ref "IC1") (pin "17") (pinfunction "OUT_17") (pintype "output"))
      (node (ref "U5") (pin "3") (pinfunction "IN1_3") (pintype "passive"))
      (node (ref "U5") (pin "4") (pinfunction "IN2_4") (pintype "passive"))
    )
    (net (code "75") (name "Net-(U5-PG)") (class "Default")
      (node (ref "R21") (pin "1") (pinfunction "1_1") (pintype "passive"))
      (node (ref "U5") (pin "8") (pinfunction "PG_8") (pintype "passive"))
    )
    (net (code "76") (name "RF-GND") (class "Default")
      (node (ref "C26") (pin "1") (pinfunction "1_1") (pintype "passive"))
      (node (ref "CB1") (pin "1") (pinfunction "1_1") (pintype "passive"))
      (node (ref "CB2") (pin "1") (pinfunction "1_1") (pintype "passive"))
      (node (ref "CON1") (pin "3") (pinfunction "GND1_3") (pintype "passive"))
      (node (ref "CON1") (pin "4") (pinfunction "GND2_4") (pintype "passive"))
      (node (ref "CON1") (pin "5") (pinfunction "GND3_5") (pintype "passive"))
      (node (ref "CON1") (pin "6") (pinfunction "GND4_6") (pintype "passive"))
      (node (ref "CX3") (pin "1") (pinfunction "1_1") (pintype "passive"))
      (node (ref "CX4") (pin "1") (pinfunction "1_1") (pintype "passive"))
      (node (ref "L1") (pin "1") (pinfunction "1_1") (pintype "passive"))
      (node (ref "T1") (pin "2") (pinfunction "DC_2") (pintype "passive"))
      (node (ref "T1") (pin "5") (pinfunction "GND_5") (pintype "passive"))
      (node (ref "T1") (pin "6") (pinfunction "GND_6") (pintype "passive"))
      (node (ref "U3") (pin "1") (pinfunction "AVSS_1") (pintype "passive"))
      (node (ref "U3") (pin "2") (pinfunction "AVSS_2") (pintype "passive"))
      (node (ref "U3") (pin "27") (pinfunction "AVSS_27") (pintype "passive"))
      (node (ref "U3") (pin "3") (pinfunction "AVSS_3") (pintype "passive"))
      (node (ref "U3") (pin "30") (pinfunction "AVSS_30") (pintype "passive"))
      (node (ref "U3") (pin "31") (pinfunction "AVSS_31") (pintype "passive"))
      (node (ref "U3") (pin "32") (pinfunction "AVSS_32") (pintype "passive"))
      (node (ref "U3") (pin "33") (pinfunction "AVSS_33") (pintype "passive"))
      (node (ref "U3") (pin "6") (pinfunction "AVSS_6") (pintype "passive"))
    )
    (net (code "77") (name "RF-VCC") (class "Default")
      (node (ref "C26") (pin "2") (pinfunction "2_2") (pintype "passive"))
      (node (ref "CB2") (pin "2") (pinfunction "2_2") (pintype "passive"))
      (node (ref "L3") (pin "2") (pinfunction "2_2") (pintype "passive"))
      (node (ref "U3") (pin "28") (pinfunction "EVDD_28") (pintype "passive"))
    )
    (net (code "78") (name "U-GND") (class "Default")
      (node (ref "L6") (pin "1") (pinfunction "1_1") (pintype "passive"))
      (node (ref "P4") (pin "ID") (pinfunction "ID_ID") (pintype "passive"))
      (node (ref "P4") (pin "SHIELD") (pinfunction "SHIELD_SHIELD") (pintype "passive"))
      (node (ref "P4") (pin "UGND") (pinfunction "UGND_UGND") (pintype "passive"))
      (node (ref "U4") (pin "1") (pinfunction "GND_1") (pintype "passive"))
    )
    (net (code "79") (name "VCC") (class "Default")
      (node (ref "C1") (pin "1") (pinfunction "1_1") (pintype "passive"))
      (node (ref "C10") (pin "1") (pinfunction "1_1") (pintype "passive"))
      (node (ref "C11") (pin "1") (pinfunction "1_1") (pintype "passive"))
      (node (ref "C13") (pin "1") (pinfunction "1_1") (pintype "passive"))
      (node (ref "C18") (pin "1") (pinfunction "1_1") (pintype "passive"))
      (node (ref "C2") (pin "1") (pinfunction "1_1") (pintype "passive"))
      (node (ref "C23") (pin "1") (pinfunction "1_1") (pintype "passive"))
      (node (ref "C29") (pin "2") (pinfunction "2_2") (pintype "passive"))
      (node (ref "C3") (pin "1") (pinfunction "1_1") (pintype "passive"))
      (node (ref "C30") (pin "2") (pinfunction "2_2") (pintype "passive"))
      (node (ref "C4") (pin "1") (pinfunction "1_1") (pintype "passive"))
      (node (ref "C7") (pin "1") (pinfunction "1_1") (pintype "passive"))
      (node (ref "C8") (pin "1") (pinfunction "1_1") (pintype "passive"))
      (node (ref "C9") (pin "1") (pinfunction "1_1") (pintype "passive"))
      (node (ref "CB4") (pin "1") (pinfunction "1_1") (pintype "passive"))
      (node (ref "F1") (pin "1") (pinfunction "X_1") (pintype "passive"))
      (node (ref "L3") (pin "1") (pinfunction "1_1") (pintype "passive"))
      (node (ref "L4") (pin "1") (pinfunction "1_1") (pintype "passive"))
      (node (ref "P1") (pin "2") (pinfunction "2_2") (pintype "passive"))
      (node (ref "P2") (pin "4") (pinfunction "4_4") (pintype "passive"))
      (node (ref "R1") (pin "2") (pinfunction "2_2") (pintype "passive"))
      (node (ref "R12") (pin "1") (pinfunction "1_1") (pintype "passive"))
      (node (ref "R13") (pin "2") (pinfunction "2_2") (pintype "passive"))
      (node (ref "R14") (pin "2") (pinfunction "2_2") (pintype "passive"))
      (node (ref "R15") (pin "2") (pinfunction "2_2") (pintype "passive"))
      (node (ref "R16") (pin "2") (pinfunction "2_2") (pintype "passive"))
      (node (ref "R17") (pin "2") (pinfunction "2_2") (pintype "passive"))
      (node (ref "R18") (pin "2") (pinfunction "2_2") (pintype "passive"))
      (node (ref "R19") (pin "2") (pinfunction "2_2") (pintype "passive"))
      (node (ref "R21") (pin "2") (pinfunction "2_2") (pintype "passive"))
      (node (ref "R22") (pin "2") (pinfunction "2_2") (pintype "passive"))
      (node (ref "U1") (pin "6") (pinfunction "VDD_6") (pintype "passive"))
      (node (ref "U1") (pin "7") (pinfunction "REGIN_7") (pintype "passive"))
      (node (ref "U2") (pin "14") (pinfunction "VCC_14") (pintype "passive"))
      (node (ref "U2") (pin "24") (pinfunction "VCC_24") (pintype "passive"))
      (node (ref "U2") (pin "34") (pinfunction "VCC_34") (pintype "passive"))
      (node (ref "U2") (pin "44") (pinfunction "VCC_44") (pintype "passive"))
      (node (ref "U2") (pin "54") (pinfunction "VCC_54") (pintype "passive"))
      (node (ref "U2") (pin "64") (pinfunction "VCC_64") (pintype "passive"))
      (node (ref "U2") (pin "74") (pinfunction "VCC_74") (pintype "passive"))
      (node (ref "U2") (pin "83") (pinfunction "VCC_83") (pintype "passive"))
      (node (ref "U3") (pin "15") (pinfunction "DEVDD_15") (pintype "passive"))
      (node (ref "U5") (pin "5") (pinfunction "OUT1_5") (pintype "passive"))
      (node (ref "U5") (pin "6") (pinfunction "OUT2_6") (pintype "passive"))
    )
    (net (code "80") (name "unconnected-(P1-Pad3)") (class "Default")
      (node (ref "P1") (pin "3") (pinfunction "3_3") (pintype "passive"))
    )
    (net (code "81") (name "unconnected-(P1-Pad4)") (class "Default")
      (node (ref "P1") (pin "4") (pinfunction "4_4") (pintype "passive"))
    )
    (net (code "82") (name "unconnected-(P2-Pad7)") (class "Default")
      (node (ref "P2") (pin "7") (pinfunction "7_7") (pintype "passive"))
    )
    (net (code "83") (name "unconnected-(P2-Pad8)") (class "Default")
      (node (ref "P2") (pin "8") (pinfunction "8_8") (pintype "passive"))
    )
    (net (code "84") (name "unconnected-(U1-NC-Pad10)") (class "Default")
      (node (ref "U1") (pin "10") (pinfunction "NC_10") (pintype "passive"))
    )
    (net (code "85") (name "unconnected-(U1-NC-Pad13)") (class "Default")
      (node (ref "U1") (pin "13") (pinfunction "NC_13") (pintype "passive"))
    )
    (net (code "86") (name "unconnected-(U1-NC-Pad14)") (class "Default")
      (node (ref "U1") (pin "14") (pinfunction "NC_14") (pintype "passive"))
    )
    (net (code "87") (name "unconnected-(U1-NC-Pad15)") (class "Default")
      (node (ref "U1") (pin "15") (pinfunction "NC_15") (pintype "passive"))
    )
    (net (code "88") (name "unconnected-(U1-NC-Pad16)") (class "Default")
      (node (ref "U1") (pin "16") (pinfunction "NC_16") (pintype "passive"))
    )
    (net (code "89") (name "unconnected-(U1-NC-Pad17)") (class "Default")
      (node (ref "U1") (pin "17") (pinfunction "NC_17") (pintype "passive"))
    )
    (net (code "90") (name "unconnected-(U1-NC-Pad18)") (class "Default")
      (node (ref "U1") (pin "18") (pinfunction "NC_18") (pintype "passive"))
    )
    (net (code "91") (name "unconnected-(U1-NC-Pad19)") (class "Default")
      (node (ref "U1") (pin "19") (pinfunction "NC_19") (pintype "passive"))
    )
    (net (code "92") (name "unconnected-(U1-NC-Pad20)") (class "Default")
      (node (ref "U1") (pin "20") (pinfunction "NC_20") (pintype "passive"))
    )
    (net (code "93") (name "unconnected-(U1-NC-Pad21)") (class "Default")
      (node (ref "U1") (pin "21") (pinfunction "NC_21") (pintype "passive"))
    )
    (net (code "94") (name "unconnected-(U1-NC-Pad22)") (class "Default")
      (node (ref "U1") (pin "22") (pinfunction "NC_22") (pintype "passive"))
    )
    (net (code "95") (name "unconnected-(U2-PA0-Pad95)") (class "Default")
      (node (ref "U2") (pin "95") (pinfunction "PA0_95") (pintype "passive"))
    )
    (net (code "96") (name "unconnected-(U2-PA1-Pad96)") (class "Default")
      (node (ref "U2") (pin "96") (pinfunction "PA1_96") (pintype "passive"))
    )
    (net (code "97") (name "unconnected-(U2-PA2-Pad97)") (class "Default")
      (node (ref "U2") (pin "97") (pinfunction "PA2_97") (pintype "passive"))
    )
    (net (code "98") (name "unconnected-(U2-PA3-Pad98)") (class "Default")
      (node (ref "U2") (pin "98") (pinfunction "PA3_98") (pintype "passive"))
    )
    (net (code "99") (name "unconnected-(U2-PA4-Pad99)") (class "Default")
      (node (ref "U2") (pin "99") (pinfunction "PA4_99") (pintype "passive"))
    )
    (net (code "100") (name "unconnected-(U2-PA5-Pad100)") (class "Default")
      (node (ref "U2") (pin "100") (pinfunction "PA5_100") (pintype "passive"))
    )
    (net (code "101") (name "unconnected-(U2-PA6-Pad1)") (class "Default")
      (node (ref "U2") (pin "1") (pinfunction "PA6_1") (pintype "passive"))
    )
    (net (code "102") (name "unconnected-(U2-PA7-Pad2)") (class "Default")
      (node (ref "U2") (pin "2") (pinfunction "PA7_2") (pintype "passive"))
    )
    (net (code "103") (name "unconnected-(U2-PB0-Pad5)") (class "Default")
      (node (ref "U2") (pin "5") (pinfunction "PB0_5") (pintype "passive"))
    )
    (net (code "104") (name "unconnected-(U2-PB1-Pad6)") (class "Default")
      (node (ref "U2") (pin "6") (pinfunction "PB1_6") (pintype "passive"))
    )
    (net (code "105") (name "unconnected-(U2-PB2-Pad7)") (class "Default")
      (node (ref "U2") (pin "7") (pinfunction "PB2_7") (pintype "passive"))
    )
    (net (code "106") (name "unconnected-(U2-PB3-Pad8)") (class "Default")
      (node (ref "U2") (pin "8") (pinfunction "PB3_8") (pintype "passive"))
    )
    (net (code "107") (name "unconnected-(U2-PD0-Pad25)") (class "Default")
      (node (ref "U2") (pin "25") (pinfunction "PD0_25") (pintype "passive"))
    )
    (net (code "108") (name "unconnected-(U2-PD1-Pad26)") (class "Default")
      (node (ref "U2") (pin "26") (pinfunction "PD1_26") (pintype "passive"))
    )
    (net (code "109") (name "unconnected-(U2-PD2-Pad27)") (class "Default")
      (node (ref "U2") (pin "27") (pinfunction "PD2_27") (pintype "passive"))
    )
    (net (code "110") (name "unconnected-(U2-PD3-Pad28)") (class "Default")
      (node (ref "U2") (pin "28") (pinfunction "PD3_28") (pintype "passive"))
    )
    (net (code "111") (name "unconnected-(U2-PD4-Pad29)") (class "Default")
      (node (ref "U2") (pin "29") (pinfunction "PD4_29") (pintype "passive"))
    )
    (net (code "112") (name "unconnected-(U2-PD5-Pad30)") (class "Default")
      (node (ref "U2") (pin "30") (pinfunction "PD5_30") (pintype "passive"))
    )
    (net (code "113") (name "unconnected-(U2-PD6-Pad31)") (class "Default")
      (node (ref "U2") (pin "31") (pinfunction "PD6_31") (pintype "passive"))
    )
    (net (code "114") (name "unconnected-(U2-PD7-Pad32)") (class "Default")
      (node (ref "U2") (pin "32") (pinfunction "PD7_32") (pintype "passive"))
    )
    (net (code "115") (name "unconnected-(U2-PE0-Pad35)") (class "Default")
      (node (ref "U2") (pin "35") (pinfunction "PE0_35") (pintype "passive"))
    )
    (net (code "116") (name "unconnected-(U2-PE1-Pad36)") (class "Default")
      (node (ref "U2") (pin "36") (pinfunction "PE1_36") (pintype "passive"))
    )
    (net (code "117") (name "unconnected-(U2-PE2-Pad37)") (class "Default")
      (node (ref "U2") (pin "37") (pinfunction "PE2_37") (pintype "passive"))
    )
    (net (code "118") (name "unconnected-(U2-PE3-Pad38)") (class "Default")
      (node (ref "U2") (pin "38") (pinfunction "PE3_38") (pintype "passive"))
    )
    (net (code "119") (name "unconnected-(U2-PE4-Pad39)") (class "Default")
      (node (ref "U2") (pin "39") (pinfunction "PE4_39") (pintype "passive"))
    )
    (net (code "120") (name "unconnected-(U2-PE5-Pad40)") (class "Default")
      (node (ref "U2") (pin "40") (pinfunction "PE5_40") (pintype "passive"))
    )
    (net (code "121") (name "unconnected-(U2-PE6-Pad41)") (class "Default")
      (node (ref "U2") (pin "41") (pinfunction "PE6_41") (pintype "passive"))
    )
    (net (code "122") (name "unconnected-(U2-PE7-Pad42)") (class "Default")
      (node (ref "U2") (pin "42") (pinfunction "PE7_42") (pintype "passive"))
    )
    (net (code "123") (name "unconnected-(U2-PF0-Pad45)") (class "Default")
      (node (ref "U2") (pin "45") (pinfunction "PF0_45") (pintype "passive"))
    )
    (net (code "124") (name "unconnected-(U2-PH0-Pad55)") (class "Default")
      (node (ref "U2") (pin "55") (pinfunction "PH0_55") (pintype "passive"))
    )
    (net (code "125") (name "unconnected-(U2-PH1-Pad56)") (class "Default")
      (node (ref "U2") (pin "56") (pinfunction "PH1_56") (pintype "passive"))
    )
    (net (code "126") (name "unconnected-(U2-PH2-Pad57)") (class "Default")
      (node (ref "U2") (pin "57") (pinfunction "PH2_57") (pintype "passive"))
    )
    (net (code "127") (name "unconnected-(U2-PH3-Pad58)") (class "Default")
      (node (ref "U2") (pin "58") (pinfunction "PH3_58") (pintype "passive"))
    )
    (net (code "128") (name "unconnected-(U2-PH4-Pad59)") (class "Default")
      (node (ref "U2") (pin "59") (pinfunction "PH4_59") (pintype "passive"))
    )
    (net (code "129") (name "unconnected-(U2-PH5-Pad60)") (class "Default")
      (node (ref "U2") (pin "60") (pinfunction "PH5_60") (pintype "passive"))
    )
    (net (code "130") (name "unconnected-(U2-PH6-Pad61)") (class "Default")
      (node (ref "U2") (pin "61") (pinfunction "PH6_61") (pintype "passive"))
    )
    (net (code "131") (name "unconnected-(U2-PH7-Pad62)") (class "Default")
      (node (ref "U2") (pin "62") (pinfunction "PH7_62") (pintype "passive"))
    )
    (net (code "132") (name "unconnected-(U2-PJ0-Pad65)") (class "Default")
      (node (ref "U2") (pin "65") (pinfunction "PJ0_65") (pintype "passive"))
    )
    (net (code "133") (name "unconnected-(U2-PJ1-Pad66)") (class "Default")
      (node (ref "U2") (pin "66") (pinfunction "PJ1_66") (pintype "passive"))
    )
    (net (code "134") (name "unconnected-(U2-PJ2-Pad67)") (class "Default")
      (node (ref "U2") (pin "67") (pinfunction "PJ2_67") (pintype "passive"))
    )
    (net (code "135") (name "unconnected-(U2-PJ3-Pad68)") (class "Default")
      (node (ref "U2") (pin "68") (pinfunction "PJ3_68") (pintype "passive"))
    )
    (net (code "136") (name "unconnected-(U2-PJ4-Pad69)") (class "Default")
      (node (ref "U2") (pin "69") (pinfunction "PJ4_69") (pintype "passive"))
    )
    (net (code "137") (name "unconnected-(U2-PJ5-Pad70)") (class "Default")
      (node (ref "U2") (pin "70") (pinfunction "PJ5_70") (pintype "passive"))
    )
    (net (code "138") (name "unconnected-(U2-PJ6-Pad71)") (class "Default")
      (node (ref "U2") (pin "71") (pinfunction "PJ6_71") (pintype "passive"))
    )
    (net (code "139") (name "unconnected-(U2-PJ7-Pad72)") (class "Default")
      (node (ref "U2") (pin "72") (pinfunction "PJ7_72") (pintype "passive"))
    )
    (net (code "140") (name "unconnected-(U2-PK0-Pad75)") (class "Default")
      (node (ref "U2") (pin "75") (pinfunction "PK0_75") (pintype "passive"))
    )
    (net (code "141") (name "unconnected-(U2-PK1-Pad76)") (class "Default")
      (node (ref "U2") (pin "76") (pinfunction "PK1_76") (pintype "passive"))
    )
    (net (code "142") (name "unconnected-(U2-PK2-Pad77)") (class "Default")
      (node (ref "U2") (pin "77") (pinfunction "PK2_77") (pintype "passive"))
    )
    (net (code "143") (name "unconnected-(U2-PK3-Pad78)") (class "Default")
      (node (ref "U2") (pin "78") (pinfunction "PK3_78") (pintype "passive"))
    )
    (net (code "144") (name "unconnected-(U2-PK4-Pad79)") (class "Default")
      (node (ref "U2") (pin "79") (pinfunction "PK4_79") (pintype "passive"))
    )
    (net (code "145") (name "unconnected-(U2-PK5-Pad80)") (class "Default")
      (node (ref "U2") (pin "80") (pinfunction "PK5_80") (pintype "passive"))
    )
    (net (code "146") (name "unconnected-(U2-PK6-Pad81)") (class "Default")
      (node (ref "U2") (pin "81") (pinfunction "PK6_81") (pintype "passive"))
    )
    (net (code "147") (name "unconnected-(U2-PK7-Pad82)") (class "Default")
      (node (ref "U2") (pin "82") (pinfunction "PK7_82") (pintype "passive"))
    )
    (net (code "148") (name "unconnected-(U2-PQ0-Pad85)") (class "Default")
      (node (ref "U2") (pin "85") (pinfunction "PQ0_85") (pintype "passive"))
    )
    (net (code "149") (name "unconnected-(U2-PQ1-Pad86)") (class "Default")
      (node (ref "U2") (pin "86") (pinfunction "PQ1_86") (pintype "passive"))
    )
    (net (code "150") (name "unconnected-(U2-PQ2-Pad87)") (class "Default")
      (node (ref "U2") (pin "87") (pinfunction "PQ2_87") (pintype "passive"))
    )
    (net (code "151") (name "unconnected-(U2-PQ3-Pad88)") (class "Default")
      (node (ref "U2") (pin "88") (pinfunction "PQ3_88") (pintype "passive"))
    )
    (net (code "152") (name "unconnected-(U5-FB-Pad7)") (class "Default")
      (node (ref "U5") (pin "7") (pinfunction "FB_7") (pintype "passive"))
    )
    (net (code "153") (name "unconnected-(Xtal1-OSC2-Pad2)") (class "Default")
      (node (ref "Xtal1") (pin "2") (pinfunction "OSC2_2") (pintype "passive"))
    )
    (net (code "154") (name "unconnected-(Xtal1-OSC2-Pad4)") (class "Default")
      (node (ref "Xtal1") (pin "4") (pinfunction "OSC2_4") (pintype "passive"))
    )
    (net (code "155") (name "unconnected-(Xtal2-OSC2-Pad2)") (class "Default")
      (node (ref "Xtal2") (pin "2") (pinfunction "OSC2_2") (pintype "passive"))
    )
    (net (code "156") (name "unconnected-(Xtal2-OSC2-Pad4)") (class "Default")
      (node (ref "Xtal2") (pin "4") (pinfunction "OSC2_4") (pintype "passive"))
    )
  )
)
